# FIT_PM_Dual_Range_AFE.net
KiCad netlist of a schematic drawn in Altium Designer
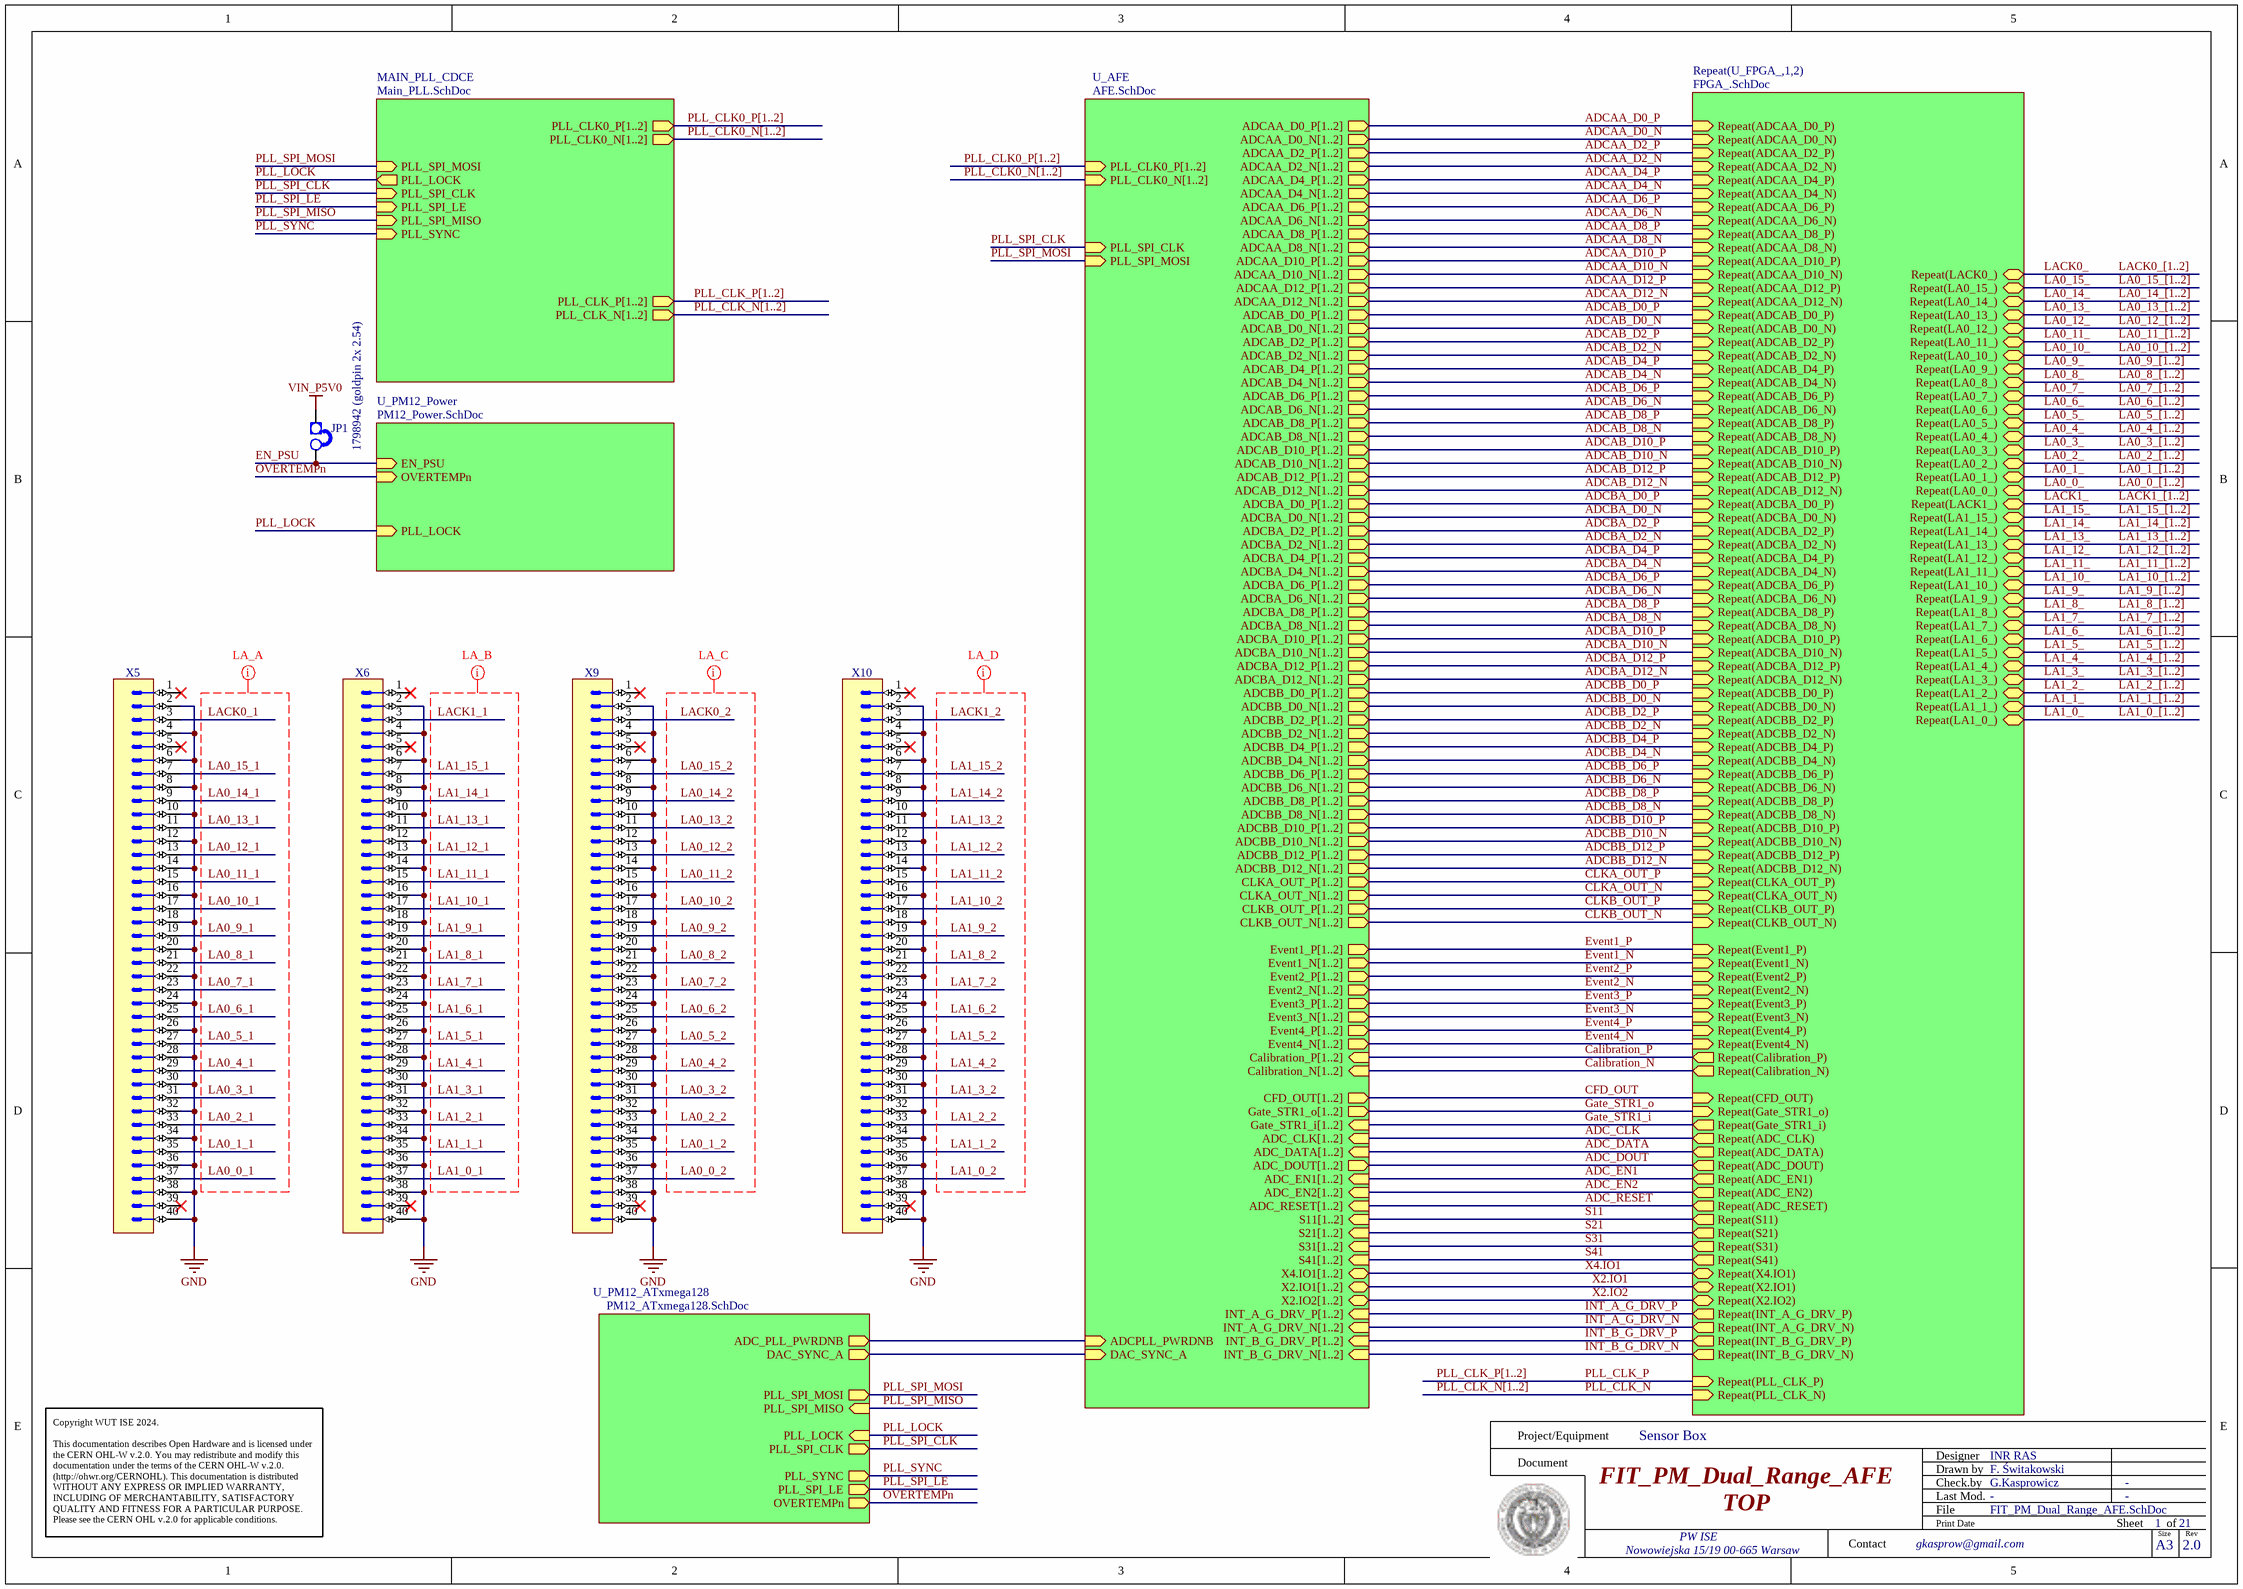
[diagram p0: FIT_PM_Dual_Range_AFE.SchDoc]

(export (version "E")
  (design (tool "Eeschema 10.0.6"))
  (components
    (comp (ref "JP1")
      (value "1798942 (goldpin 2x 2.54)")
      (footprint "jump")
      (description "Jumper")
      (fields (field (name "MANUFACTURER PART NUMBER") "68001-102HLF"))
      (libsource (lib "LIBRARY_SCH") (part "JUMPER"))
    )
    (comp (ref "X5")
      (value "~")
      (footprint "CONNFLY_DS1013-40SSIB1-B-0")
      (description "Connector 40 Male")
      (fields
        (field (name "PART NUMBER") "CONNFLY_DS1013-40SSIB1-B-0")
        (field (name "MANUFACTURER") "CONNFLY")
        (field (name "AUTHOR") "CERN DEM HF")
      )
      (libsource (lib "Connectors") (part "Connector 40 Male"))
    )
    (comp (ref "X6")
      (value "~")
      (footprint "CONNFLY_DS1013-40SSIB1-B-0")
      (description "Connector 40 Male")
      (fields
        (field (name "PART NUMBER") "CONNFLY_DS1013-40SSIB1-B-0")
        (field (name "MANUFACTURER") "CONNFLY")
        (field (name "AUTHOR") "CERN DEM HF")
      )
      (libsource (lib "Connectors") (part "Connector 40 Male"))
    )
    (comp (ref "X9")
      (value "~")
      (footprint "CONNFLY_DS1013-40SSIB1-B-0")
      (description "Connector 40 Male")
      (fields
        (field (name "PART NUMBER") "CONNFLY_DS1013-40SSIB1-B-0")
        (field (name "MANUFACTURER") "CONNFLY")
        (field (name "AUTHOR") "CERN DEM HF")
      )
      (libsource (lib "Connectors") (part "Connector 40 Male"))
    )
    (comp (ref "X10")
      (value "~")
      (footprint "CONNFLY_DS1013-40SSIB1-B-0")
      (description "Connector 40 Male")
      (fields
        (field (name "PART NUMBER") "CONNFLY_DS1013-40SSIB1-B-0")
        (field (name "MANUFACTURER") "CONNFLY")
        (field (name "AUTHOR") "CERN DEM HF")
      )
      (libsource (lib "Connectors") (part "Connector 40 Male"))
    )
  )
  (nets
    (net (code "149") (name "/EN_PSU") (class "Default")
      (node (ref "JP1") (pin "2") (pinfunction "E2_2") (pintype "passive"))
    )
    (net (code "179") (name "/LA0_0_1") (class "Default")
      (node (ref "X5") (pin "37") (pinfunction "37_37") (pintype "bidirectional"))
    )
    (net (code "180") (name "/LA0_0_2") (class "Default")
      (node (ref "X9") (pin "37") (pinfunction "37_37") (pintype "bidirectional"))
    )
    (net (code "183") (name "/LA0_1_1") (class "Default")
      (node (ref "X5") (pin "35") (pinfunction "35_35") (pintype "bidirectional"))
    )
    (net (code "184") (name "/LA0_1_2") (class "Default")
      (node (ref "X9") (pin "35") (pinfunction "35_35") (pintype "bidirectional"))
    )
    (net (code "187") (name "/LA0_2_1") (class "Default")
      (node (ref "X5") (pin "33") (pinfunction "33_33") (pintype "bidirectional"))
    )
    (net (code "188") (name "/LA0_2_2") (class "Default")
      (node (ref "X9") (pin "33") (pinfunction "33_33") (pintype "bidirectional"))
    )
    (net (code "191") (name "/LA0_3_1") (class "Default")
      (node (ref "X5") (pin "31") (pinfunction "31_31") (pintype "bidirectional"))
    )
    (net (code "192") (name "/LA0_3_2") (class "Default")
      (node (ref "X9") (pin "31") (pinfunction "31_31") (pintype "bidirectional"))
    )
    (net (code "195") (name "/LA0_4_1") (class "Default")
      (node (ref "X5") (pin "29") (pinfunction "29_29") (pintype "bidirectional"))
    )
    (net (code "196") (name "/LA0_4_2") (class "Default")
      (node (ref "X9") (pin "29") (pinfunction "29_29") (pintype "bidirectional"))
    )
    (net (code "199") (name "/LA0_5_1") (class "Default")
      (node (ref "X5") (pin "27") (pinfunction "27_27") (pintype "bidirectional"))
    )
    (net (code "200") (name "/LA0_5_2") (class "Default")
      (node (ref "X9") (pin "27") (pinfunction "27_27") (pintype "bidirectional"))
    )
    (net (code "203") (name "/LA0_6_1") (class "Default")
      (node (ref "X5") (pin "25") (pinfunction "25_25") (pintype "bidirectional"))
    )
    (net (code "204") (name "/LA0_6_2") (class "Default")
      (node (ref "X9") (pin "25") (pinfunction "25_25") (pintype "bidirectional"))
    )
    (net (code "207") (name "/LA0_7_1") (class "Default")
      (node (ref "X5") (pin "23") (pinfunction "23_23") (pintype "bidirectional"))
    )
    (net (code "208") (name "/LA0_7_2") (class "Default")
      (node (ref "X9") (pin "23") (pinfunction "23_23") (pintype "bidirectional"))
    )
    (net (code "211") (name "/LA0_8_1") (class "Default")
      (node (ref "X5") (pin "21") (pinfunction "21_21") (pintype "bidirectional"))
    )
    (net (code "212") (name "/LA0_8_2") (class "Default")
      (node (ref "X9") (pin "21") (pinfunction "21_21") (pintype "bidirectional"))
    )
    (net (code "215") (name "/LA0_9_1") (class "Default")
      (node (ref "X5") (pin "19") (pinfunction "19_19") (pintype "bidirectional"))
    )
    (net (code "216") (name "/LA0_9_2") (class "Default")
      (node (ref "X9") (pin "19") (pinfunction "19_19") (pintype "bidirectional"))
    )
    (net (code "219") (name "/LA0_10_1") (class "Default")
      (node (ref "X5") (pin "17") (pinfunction "17_17") (pintype "bidirectional"))
    )
    (net (code "220") (name "/LA0_10_2") (class "Default")
      (node (ref "X9") (pin "17") (pinfunction "17_17") (pintype "bidirectional"))
    )
    (net (code "223") (name "/LA0_11_1") (class "Default")
      (node (ref "X5") (pin "15") (pinfunction "15_15") (pintype "bidirectional"))
    )
    (net (code "224") (name "/LA0_11_2") (class "Default")
      (node (ref "X9") (pin "15") (pinfunction "15_15") (pintype "bidirectional"))
    )
    (net (code "227") (name "/LA0_12_1") (class "Default")
      (node (ref "X5") (pin "13") (pinfunction "13_13") (pintype "bidirectional"))
    )
    (net (code "228") (name "/LA0_12_2") (class "Default")
      (node (ref "X9") (pin "13") (pinfunction "13_13") (pintype "bidirectional"))
    )
    (net (code "231") (name "/LA0_13_1") (class "Default")
      (node (ref "X5") (pin "11") (pinfunction "11_11") (pintype "bidirectional"))
    )
    (net (code "232") (name "/LA0_13_2") (class "Default")
      (node (ref "X9") (pin "11") (pinfunction "11_11") (pintype "bidirectional"))
    )
    (net (code "235") (name "/LA0_14_1") (class "Default")
      (node (ref "X5") (pin "9") (pinfunction "9_9") (pintype "bidirectional"))
    )
    (net (code "236") (name "/LA0_14_2") (class "Default")
      (node (ref "X9") (pin "9") (pinfunction "9_9") (pintype "bidirectional"))
    )
    (net (code "239") (name "/LA0_15_1") (class "Default")
      (node (ref "X5") (pin "7") (pinfunction "7_7") (pintype "bidirectional"))
    )
    (net (code "240") (name "/LA0_15_2") (class "Default")
      (node (ref "X9") (pin "7") (pinfunction "7_7") (pintype "bidirectional"))
    )
    (net (code "243") (name "/LA1_0_1") (class "Default")
      (node (ref "X6") (pin "37") (pinfunction "37_37") (pintype "bidirectional"))
    )
    (net (code "244") (name "/LA1_0_2") (class "Default")
      (node (ref "X10") (pin "37") (pinfunction "37_37") (pintype "bidirectional"))
    )
    (net (code "247") (name "/LA1_1_1") (class "Default")
      (node (ref "X6") (pin "35") (pinfunction "35_35") (pintype "bidirectional"))
    )
    (net (code "248") (name "/LA1_1_2") (class "Default")
      (node (ref "X10") (pin "35") (pinfunction "35_35") (pintype "bidirectional"))
    )
    (net (code "251") (name "/LA1_2_1") (class "Default")
      (node (ref "X6") (pin "33") (pinfunction "33_33") (pintype "bidirectional"))
    )
    (net (code "252") (name "/LA1_2_2") (class "Default")
      (node (ref "X10") (pin "33") (pinfunction "33_33") (pintype "bidirectional"))
    )
    (net (code "255") (name "/LA1_3_1") (class "Default")
      (node (ref "X6") (pin "31") (pinfunction "31_31") (pintype "bidirectional"))
    )
    (net (code "256") (name "/LA1_3_2") (class "Default")
      (node (ref "X10") (pin "31") (pinfunction "31_31") (pintype "bidirectional"))
    )
    (net (code "259") (name "/LA1_4_1") (class "Default")
      (node (ref "X6") (pin "29") (pinfunction "29_29") (pintype "bidirectional"))
    )
    (net (code "260") (name "/LA1_4_2") (class "Default")
      (node (ref "X10") (pin "29") (pinfunction "29_29") (pintype "bidirectional"))
    )
    (net (code "263") (name "/LA1_5_1") (class "Default")
      (node (ref "X6") (pin "27") (pinfunction "27_27") (pintype "bidirectional"))
    )
    (net (code "264") (name "/LA1_5_2") (class "Default")
      (node (ref "X10") (pin "27") (pinfunction "27_27") (pintype "bidirectional"))
    )
    (net (code "267") (name "/LA1_6_1") (class "Default")
      (node (ref "X6") (pin "25") (pinfunction "25_25") (pintype "bidirectional"))
    )
    (net (code "268") (name "/LA1_6_2") (class "Default")
      (node (ref "X10") (pin "25") (pinfunction "25_25") (pintype "bidirectional"))
    )
    (net (code "271") (name "/LA1_7_1") (class "Default")
      (node (ref "X6") (pin "23") (pinfunction "23_23") (pintype "bidirectional"))
    )
    (net (code "272") (name "/LA1_7_2") (class "Default")
      (node (ref "X10") (pin "23") (pinfunction "23_23") (pintype "bidirectional"))
    )
    (net (code "275") (name "/LA1_8_1") (class "Default")
      (node (ref "X6") (pin "21") (pinfunction "21_21") (pintype "bidirectional"))
    )
    (net (code "276") (name "/LA1_8_2") (class "Default")
      (node (ref "X10") (pin "21") (pinfunction "21_21") (pintype "bidirectional"))
    )
    (net (code "279") (name "/LA1_9_1") (class "Default")
      (node (ref "X6") (pin "19") (pinfunction "19_19") (pintype "bidirectional"))
    )
    (net (code "280") (name "/LA1_9_2") (class "Default")
      (node (ref "X10") (pin "19") (pinfunction "19_19") (pintype "bidirectional"))
    )
    (net (code "283") (name "/LA1_10_1") (class "Default")
      (node (ref "X6") (pin "17") (pinfunction "17_17") (pintype "bidirectional"))
    )
    (net (code "284") (name "/LA1_10_2") (class "Default")
      (node (ref "X10") (pin "17") (pinfunction "17_17") (pintype "bidirectional"))
    )
    (net (code "287") (name "/LA1_11_1") (class "Default")
      (node (ref "X6") (pin "15") (pinfunction "15_15") (pintype "bidirectional"))
    )
    (net (code "288") (name "/LA1_11_2") (class "Default")
      (node (ref "X10") (pin "15") (pinfunction "15_15") (pintype "bidirectional"))
    )
    (net (code "291") (name "/LA1_12_1") (class "Default")
      (node (ref "X6") (pin "13") (pinfunction "13_13") (pintype "bidirectional"))
    )
    (net (code "292") (name "/LA1_12_2") (class "Default")
      (node (ref "X10") (pin "13") (pinfunction "13_13") (pintype "bidirectional"))
    )
    (net (code "295") (name "/LA1_13_1") (class "Default")
      (node (ref "X6") (pin "11") (pinfunction "11_11") (pintype "bidirectional"))
    )
    (net (code "296") (name "/LA1_13_2") (class "Default")
      (node (ref "X10") (pin "11") (pinfunction "11_11") (pintype "bidirectional"))
    )
    (net (code "299") (name "/LA1_14_1") (class "Default")
      (node (ref "X6") (pin "9") (pinfunction "9_9") (pintype "bidirectional"))
    )
    (net (code "300") (name "/LA1_14_2") (class "Default")
      (node (ref "X10") (pin "9") (pinfunction "9_9") (pintype "bidirectional"))
    )
    (net (code "303") (name "/LA1_15_1") (class "Default")
      (node (ref "X6") (pin "7") (pinfunction "7_7") (pintype "bidirectional"))
    )
    (net (code "304") (name "/LA1_15_2") (class "Default")
      (node (ref "X10") (pin "7") (pinfunction "7_7") (pintype "bidirectional"))
    )
    (net (code "307") (name "/LACK0_1") (class "Default")
      (node (ref "X5") (pin "3") (pinfunction "3_3") (pintype "bidirectional"))
    )
    (net (code "308") (name "/LACK0_2") (class "Default")
      (node (ref "X9") (pin "3") (pinfunction "3_3") (pintype "bidirectional"))
    )
    (net (code "311") (name "/LACK1_1") (class "Default")
      (node (ref "X6") (pin "3") (pinfunction "3_3") (pintype "bidirectional"))
    )
    (net (code "312") (name "/LACK1_2") (class "Default")
      (node (ref "X10") (pin "3") (pinfunction "3_3") (pintype "bidirectional"))
    )
    (net (code "341") (name "GND") (class "Default")
      (node (ref "X10") (pin "10") (pinfunction "10_10") (pintype "bidirectional"))
      (node (ref "X10") (pin "12") (pinfunction "12_12") (pintype "bidirectional"))
      (node (ref "X10") (pin "14") (pinfunction "14_14") (pintype "bidirectional"))
      (node (ref "X10") (pin "16") (pinfunction "16_16") (pintype "bidirectional"))
      (node (ref "X10") (pin "18") (pinfunction "18_18") (pintype "bidirectional"))
      (node (ref "X10") (pin "2") (pinfunction "2_2") (pintype "bidirectional"))
      (node (ref "X10") (pin "20") (pinfunction "20_20") (pintype "bidirectional"))
      (node (ref "X10") (pin "22") (pinfunction "22_22") (pintype "bidirectional"))
      (node (ref "X10") (pin "24") (pinfunction "24_24") (pintype "bidirectional"))
      (node (ref "X10") (pin "26") (pinfunction "26_26") (pintype "bidirectional"))
      (node (ref "X10") (pin "28") (pinfunction "28_28") (pintype "bidirectional"))
      (node (ref "X10") (pin "30") (pinfunction "30_30") (pintype "bidirectional"))
      (node (ref "X10") (pin "32") (pinfunction "32_32") (pintype "bidirectional"))
      (node (ref "X10") (pin "34") (pinfunction "34_34") (pintype "bidirectional"))
      (node (ref "X10") (pin "36") (pinfunction "36_36") (pintype "bidirectional"))
      (node (ref "X10") (pin "38") (pinfunction "38_38") (pintype "bidirectional"))
      (node (ref "X10") (pin "4") (pinfunction "4_4") (pintype "bidirectional"))
      (node (ref "X10") (pin "40") (pinfunction "40_40") (pintype "bidirectional"))
      (node (ref "X10") (pin "6") (pinfunction "6_6") (pintype "bidirectional"))
      (node (ref "X10") (pin "8") (pinfunction "8_8") (pintype "bidirectional"))
      (node (ref "X5") (pin "10") (pinfunction "10_10") (pintype "bidirectional"))
      (node (ref "X5") (pin "12") (pinfunction "12_12") (pintype "bidirectional"))
      (node (ref "X5") (pin "14") (pinfunction "14_14") (pintype "bidirectional"))
      (node (ref "X5") (pin "16") (pinfunction "16_16") (pintype "bidirectional"))
      (node (ref "X5") (pin "18") (pinfunction "18_18") (pintype "bidirectional"))
      (node (ref "X5") (pin "2") (pinfunction "2_2") (pintype "bidirectional"))
      (node (ref "X5") (pin "20") (pinfunction "20_20") (pintype "bidirectional"))
      (node (ref "X5") (pin "22") (pinfunction "22_22") (pintype "bidirectional"))
      (node (ref "X5") (pin "24") (pinfunction "24_24") (pintype "bidirectional"))
      (node (ref "X5") (pin "26") (pinfunction "26_26") (pintype "bidirectional"))
      (node (ref "X5") (pin "28") (pinfunction "28_28") (pintype "bidirectional"))
      (node (ref "X5") (pin "30") (pinfunction "30_30") (pintype "bidirectional"))
      (node (ref "X5") (pin "32") (pinfunction "32_32") (pintype "bidirectional"))
      (node (ref "X5") (pin "34") (pinfunction "34_34") (pintype "bidirectional"))
      (node (ref "X5") (pin "36") (pinfunction "36_36") (pintype "bidirectional"))
      (node (ref "X5") (pin "38") (pinfunction "38_38") (pintype "bidirectional"))
      (node (ref "X5") (pin "4") (pinfunction "4_4") (pintype "bidirectional"))
      (node (ref "X5") (pin "40") (pinfunction "40_40") (pintype "bidirectional"))
      (node (ref "X5") (pin "6") (pinfunction "6_6") (pintype "bidirectional"))
      (node (ref "X5") (pin "8") (pinfunction "8_8") (pintype "bidirectional"))
      (node (ref "X6") (pin "10") (pinfunction "10_10") (pintype "bidirectional"))
      (node (ref "X6") (pin "12") (pinfunction "12_12") (pintype "bidirectional"))
      (node (ref "X6") (pin "14") (pinfunction "14_14") (pintype "bidirectional"))
      (node (ref "X6") (pin "16") (pinfunction "16_16") (pintype "bidirectional"))
      (node (ref "X6") (pin "18") (pinfunction "18_18") (pintype "bidirectional"))
      (node (ref "X6") (pin "2") (pinfunction "2_2") (pintype "bidirectional"))
      (node (ref "X6") (pin "20") (pinfunction "20_20") (pintype "bidirectional"))
      (node (ref "X6") (pin "22") (pinfunction "22_22") (pintype "bidirectional"))
      (node (ref "X6") (pin "24") (pinfunction "24_24") (pintype "bidirectional"))
      (node (ref "X6") (pin "26") (pinfunction "26_26") (pintype "bidirectional"))
      (node (ref "X6") (pin "28") (pinfunction "28_28") (pintype "bidirectional"))
      (node (ref "X6") (pin "30") (pinfunction "30_30") (pintype "bidirectional"))
      (node (ref "X6") (pin "32") (pinfunction "32_32") (pintype "bidirectional"))
      (node (ref "X6") (pin "34") (pinfunction "34_34") (pintype "bidirectional"))
      (node (ref "X6") (pin "36") (pinfunction "36_36") (pintype "bidirectional"))
      (node (ref "X6") (pin "38") (pinfunction "38_38") (pintype "bidirectional"))
      (node (ref "X6") (pin "4") (pinfunction "4_4") (pintype "bidirectional"))
      (node (ref "X6") (pin "40") (pinfunction "40_40") (pintype "bidirectional"))
      (node (ref "X6") (pin "6") (pinfunction "6_6") (pintype "bidirectional"))
      (node (ref "X6") (pin "8") (pinfunction "8_8") (pintype "bidirectional"))
      (node (ref "X9") (pin "10") (pinfunction "10_10") (pintype "bidirectional"))
      (node (ref "X9") (pin "12") (pinfunction "12_12") (pintype "bidirectional"))
      (node (ref "X9") (pin "14") (pinfunction "14_14") (pintype "bidirectional"))
      (node (ref "X9") (pin "16") (pinfunction "16_16") (pintype "bidirectional"))
      (node (ref "X9") (pin "18") (pinfunction "18_18") (pintype "bidirectional"))
      (node (ref "X9") (pin "2") (pinfunction "2_2") (pintype "bidirectional"))
      (node (ref "X9") (pin "20") (pinfunction "20_20") (pintype "bidirectional"))
      (node (ref "X9") (pin "22") (pinfunction "22_22") (pintype "bidirectional"))
      (node (ref "X9") (pin "24") (pinfunction "24_24") (pintype "bidirectional"))
      (node (ref "X9") (pin "26") (pinfunction "26_26") (pintype "bidirectional"))
      (node (ref "X9") (pin "28") (pinfunction "28_28") (pintype "bidirectional"))
      (node (ref "X9") (pin "30") (pinfunction "30_30") (pintype "bidirectional"))
      (node (ref "X9") (pin "32") (pinfunction "32_32") (pintype "bidirectional"))
      (node (ref "X9") (pin "34") (pinfunction "34_34") (pintype "bidirectional"))
      (node (ref "X9") (pin "36") (pinfunction "36_36") (pintype "bidirectional"))
      (node (ref "X9") (pin "38") (pinfunction "38_38") (pintype "bidirectional"))
      (node (ref "X9") (pin "4") (pinfunction "4_4") (pintype "bidirectional"))
      (node (ref "X9") (pin "40") (pinfunction "40_40") (pintype "bidirectional"))
      (node (ref "X9") (pin "6") (pinfunction "6_6") (pintype "bidirectional"))
      (node (ref "X9") (pin "8") (pinfunction "8_8") (pintype "bidirectional"))
    )
    (net (code "342") (name "VIN_P5V0") (class "Default")
      (node (ref "JP1") (pin "1") (pinfunction "E1_1") (pintype "passive"))
    )
    (net (code "343") (name "unconnected-(X5-Pad1)") (class "Default")
      (node (ref "X5") (pin "1") (pinfunction "1_1") (pintype "bidirectional+no_connect"))
    )
    (net (code "344") (name "unconnected-(X5-Pad5)") (class "Default")
      (node (ref "X5") (pin "5") (pinfunction "5_5") (pintype "bidirectional+no_connect"))
    )
    (net (code "345") (name "unconnected-(X5-Pad39)") (class "Default")
      (node (ref "X5") (pin "39") (pinfunction "39_39") (pintype "bidirectional+no_connect"))
    )
    (net (code "346") (name "unconnected-(X6-Pad1)") (class "Default")
      (node (ref "X6") (pin "1") (pinfunction "1_1") (pintype "bidirectional+no_connect"))
    )
    (net (code "347") (name "unconnected-(X6-Pad5)") (class "Default")
      (node (ref "X6") (pin "5") (pinfunction "5_5") (pintype "bidirectional+no_connect"))
    )
    (net (code "348") (name "unconnected-(X6-Pad39)") (class "Default")
      (node (ref "X6") (pin "39") (pinfunction "39_39") (pintype "bidirectional+no_connect"))
    )
    (net (code "349") (name "unconnected-(X9-Pad1)") (class "Default")
      (node (ref "X9") (pin "1") (pinfunction "1_1") (pintype "bidirectional+no_connect"))
    )
    (net (code "350") (name "unconnected-(X9-Pad5)") (class "Default")
      (node (ref "X9") (pin "5") (pinfunction "5_5") (pintype "bidirectional+no_connect"))
    )
    (net (code "351") (name "unconnected-(X9-Pad39)") (class "Default")
      (node (ref "X9") (pin "39") (pinfunction "39_39") (pintype "bidirectional+no_connect"))
    )
    (net (code "352") (name "unconnected-(X10-Pad1)") (class "Default")
      (node (ref "X10") (pin "1") (pinfunction "1_1") (pintype "bidirectional+no_connect"))
    )
    (net (code "353") (name "unconnected-(X10-Pad5)") (class "Default")
      (node (ref "X10") (pin "5") (pinfunction "5_5") (pintype "bidirectional+no_connect"))
    )
    (net (code "354") (name "unconnected-(X10-Pad39)") (class "Default")
      (node (ref "X10") (pin "39") (pinfunction "39_39") (pintype "bidirectional+no_connect"))
    )
  )
)
